# SSDR.net
KiCad netlist of a schematic drawn in Altium Designer
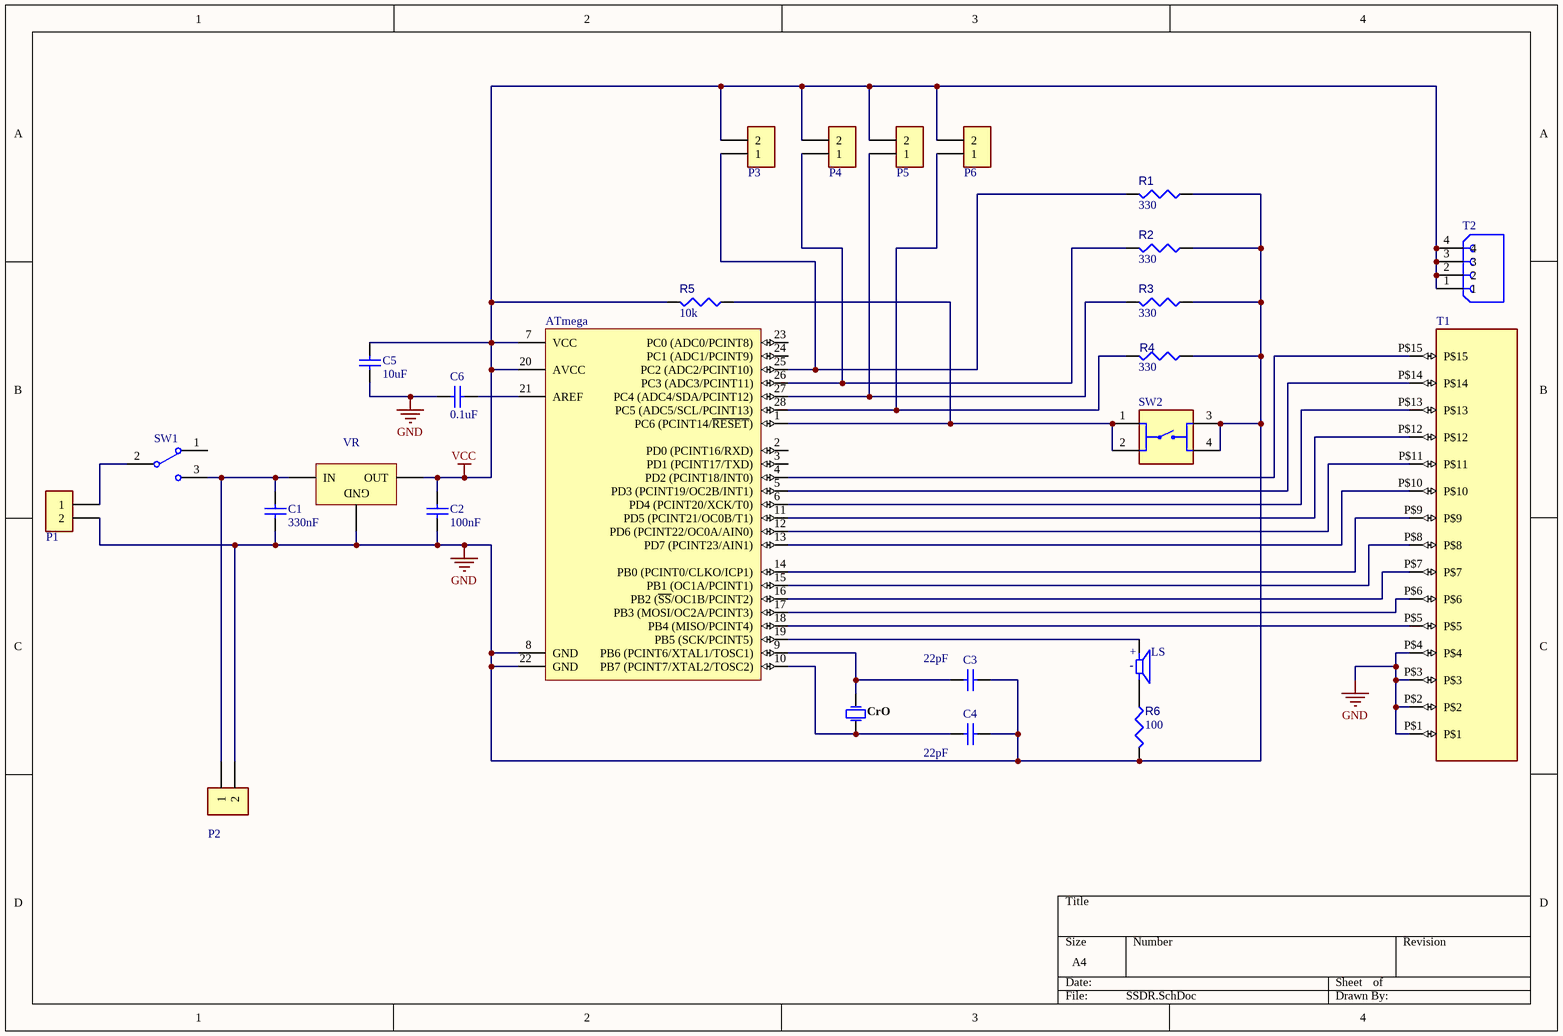
[diagram p0: SSDR.SchDoc]

(export (version "E")
  (design (tool "Eeschema 10.0.6"))
  (components
    (comp (ref "ATmega")
      (value "ATMEGA328P-PU")
      (footprint "ATML-28P3")
      (fields (field (name "MANUFACTURER") "Atmel"))
      (libsource (lib "University of Moratuwa") (part "MC-8B-ATM48-IL28"))
    )
    (comp (ref "C1")
      (value "330nF")
      (footprint "KEMT-C315-THT-2")
      (description "Capacitor, Ceramic, 22 pF, +/-10 %, 100 V, -55 to 125 degC, 2-Pin THD, RoHS, Bulk")
      (libsource (lib "Altium Content Vault") (part "CAP-NP-2"))
    )
    (comp (ref "C2")
      (value "100nF")
      (footprint "KEMT-C315-THT-2")
      (description "Capacitor, Ceramic, 22 pF, +/-10 %, 100 V, -55 to 125 degC, 2-Pin THD, RoHS, Bulk")
      (libsource (lib "Altium Content Vault") (part "CAP-NP-2"))
    )
    (comp (ref "C3")
      (value "22pF")
      (footprint "KEMT-C315-THT-2")
      (description "Capacitor, Ceramic, 22 pF, +/-10 %, 100 V, -55 to 125 degC, 2-Pin THD, RoHS, Bulk")
      (libsource (lib "Altium Content Vault") (part "CAP-NP-2"))
    )
    (comp (ref "C4")
      (value "22pF")
      (footprint "KEMT-C315-THT-2")
      (description "Capacitor, Ceramic, 22 pF, +/-10 %, 100 V, -55 to 125 degC, 2-Pin THD, RoHS, Bulk")
      (libsource (lib "Altium Content Vault") (part "CAP-NP-2"))
    )
    (comp (ref "C5")
      (value "10uF")
      (footprint "KEMT-C315-THT-2")
      (description "Capacitor, Ceramic, 22 pF, +/-10 %, 100 V, -55 to 125 degC, 2-Pin THD, RoHS, Bulk")
      (libsource (lib "Altium Content Vault") (part "CAP-NP-2"))
    )
    (comp (ref "C6")
      (value "0.1uF")
      (footprint "KEMT-C315-THT-2")
      (description "Capacitor, Ceramic, 22 pF, +/-10 %, 100 V, -55 to 125 degC, 2-Pin THD, RoHS, Bulk")
      (libsource (lib "Altium Content Vault") (part "CAP-NP-2"))
    )
    (comp (ref "CrO")
      (value "FOXSLF/160-20")
      (footprint "FOX-FOXSLF160-20")
      (description "Resistance Weld Thru-Hole Crystal, 16 MHz, -20 to 70 degC, 2-Pin THD, RoHS, Bulk")
      (fields (field (name "TOLERANCE") "1%"))
      (libsource (lib "Altium Content Vault") (part "XTAL-1-2-2"))
    )
    (comp (ref "LS")
      (value "PKM17EPP-2002-B0")
      (footprint "SPKR_PKM17EPP-2002-B0")
      (description "Buzzers Transducer, Externally Driven Piezo 3V 2kHz 70dB @ 3V, 10cm Through Hole PC Pins")
      (libsource (lib "University of Moratuwa") (part "PKM17EPP-2002-B0"))
    )
    (comp (ref "P1")
      (value "282837-2")
      (footprint "TE_282837-2")
      (fields (field (name "MF") "TE Connectivity"))
      (libsource (lib "") (part "282837-2_2"))
    )
    (comp (ref "P2")
      (value "282837-2")
      (footprint "TE_282837-2")
      (fields (field (name "MF") "TE Connectivity"))
      (libsource (lib "") (part "282837-2_1"))
    )
    (comp (ref "P3")
      (value "282837-2")
      (footprint "TE_282837-2")
      (fields (field (name "MF") "TE Connectivity"))
      (libsource (lib "University of Moratuwa") (part "282837-2"))
    )
    (comp (ref "P4")
      (value "282837-2")
      (footprint "TE_282837-2")
      (fields (field (name "MF") "TE Connectivity"))
      (libsource (lib "University of Moratuwa") (part "282837-2"))
    )
    (comp (ref "P5")
      (value "282837-2")
      (footprint "TE_282837-2")
      (fields (field (name "MF") "TE Connectivity"))
      (libsource (lib "University of Moratuwa") (part "282837-2"))
    )
    (comp (ref "P6")
      (value "282837-2")
      (footprint "TE_282837-2")
      (fields (field (name "MF") "TE Connectivity"))
      (libsource (lib "University of Moratuwa") (part "282837-2"))
    )
    (comp (ref "R1")
      (value "330")
      (footprint "RESA60-630X240")
      (description "RES 470K OHM 5% 1/4W AXIAL")
      (fields (field (name "POWER") "250mW") (field (name "TOLERANCE") "1%"))
      (libsource (lib "University of Moratuwa") (part "RES-2"))
    )
    (comp (ref "R2")
      (value "330")
      (footprint "RESA60-630X240")
      (description "RES 470K OHM 5% 1/4W AXIAL")
      (fields (field (name "POWER") "250mW") (field (name "TOLERANCE") "1%"))
      (libsource (lib "University of Moratuwa") (part "RES-2"))
    )
    (comp (ref "R3")
      (value "330")
      (footprint "RESA60-630X240")
      (description "RES 470K OHM 5% 1/4W AXIAL")
      (fields (field (name "POWER") "250mW") (field (name "TOLERANCE") "1%"))
      (libsource (lib "University of Moratuwa") (part "RES-2"))
    )
    (comp (ref "R4")
      (value "330")
      (footprint "RESA60-630X240")
      (description "RES 470K OHM 5% 1/4W AXIAL")
      (fields (field (name "POWER") "250mW") (field (name "TOLERANCE") "1%"))
      (libsource (lib "University of Moratuwa") (part "RES-2"))
    )
    (comp (ref "R5")
      (value "10k")
      (footprint "RESA60-630X240")
      (description "RES 470K OHM 5% 1/4W AXIAL")
      (fields (field (name "POWER") "250mW") (field (name "TOLERANCE") "1%"))
      (libsource (lib "University of Moratuwa") (part "RES-2"))
    )
    (comp (ref "R6")
      (value "100")
      (footprint "RESA60-630X240")
      (description "RES 470K OHM 5% 1/4W AXIAL")
      (fields (field (name "POWER") "250mW") (field (name "TOLERANCE") "1%"))
      (libsource (lib "University of Moratuwa") (part "RES-2"))
    )
    (comp (ref "SW1")
      (value "EG1218")
      (footprint "ESWI-EG1218_V")
      (description "Slide Switch, SPDT, 500 V, -20 to 70 degC, 3-Pin THD, RoHS, Bulk")
      (fields (field (name "MANUFACTURER") "E-Switch"))
      (libsource (lib "University of Moratuwa") (part "SW-SPDT-3_B"))
    )
    (comp (ref "SW2")
      (value "1825910-6")
      (footprint "SW_1825910-6-4")
      (description "Switch Push Button OFF (ON) SPST Round Button 0.05A 24VDC Momentary Contact PC Pins Thru-Hole")
      (fields (field (name "DIGI-KEY_PART_NUMBER") "450-1650-ND") (field (name "MF") "TE Connectivity"))
      (libsource (lib "University of Moratuwa") (part "1825910-6"))
    )
    (comp (ref "T1")
      (value "PPTC151LFBN-RC")
      (footprint "PPTC151LFBN-RC")
      (description "15 Position Header Connector Through Hole")
      (fields (field (name "MF") "Sullins Connector"))
      (libsource (lib "University of Moratuwa") (part "PPTC151LFBN-RC"))
    )
    (comp (ref "T2")
      (value "PPTC041LFBN-RC")
      (footprint "SULLINS_PPTC041LFBN-RC")
      (description "4 Position Header Connector 0.100 (2.54mm) Through Hole Tin")
      (fields (field (name "MF") "Sullins Connector") (field (name "DIGI-KEY_PART_NUMBER") "S7002-ND"))
      (libsource (lib "University of Moratuwa") (part "PPTC041LFBN-RC"))
    )
    (comp (ref "VR")
      (value "L7805CV")
      (footprint "TO220")
      (fields (field (name "MANUFACTURER") "STMicroelectronics"))
      (libsource (lib "University of Moratuwa") (part "PM-REG-L4940-SIL3"))
    )
  )
  (nets
    (net (code "1") (name "GND") (class "Default")
      (node (ref "ATmega") (pin "22") (pinfunction "GND_22") (pintype "power_in"))
      (node (ref "ATmega") (pin "8") (pinfunction "GND_8") (pintype "power_in"))
      (node (ref "C1") (pin "1") (pinfunction "1_1") (pintype "passive"))
      (node (ref "C2") (pin "1") (pinfunction "1_1") (pintype "passive"))
      (node (ref "C3") (pin "2") (pinfunction "2_2") (pintype "passive"))
      (node (ref "C4") (pin "2") (pinfunction "2_2") (pintype "passive"))
      (node (ref "C5") (pin "1") (pinfunction "1_1") (pintype "passive"))
      (node (ref "C6") (pin "2") (pinfunction "2_2") (pintype "passive"))
      (node (ref "P1") (pin "2") (pinfunction "2_2") (pintype "passive"))
      (node (ref "P2") (pin "2") (pinfunction "2_2") (pintype "passive"))
      (node (ref "R1") (pin "1") (pinfunction "1_1") (pintype "passive"))
      (node (ref "R2") (pin "1") (pinfunction "1_1") (pintype "passive"))
      (node (ref "R3") (pin "1") (pinfunction "1_1") (pintype "passive"))
      (node (ref "R4") (pin "1") (pinfunction "1_1") (pintype "passive"))
      (node (ref "R6") (pin "2") (pinfunction "2_2") (pintype "passive"))
      (node (ref "SW2") (pin "3") (pinfunction "3_3") (pintype "passive"))
      (node (ref "SW2") (pin "4") (pinfunction "4_4") (pintype "passive"))
      (node (ref "T1") (pin "P$1") (pinfunction "P$1_P$1") (pintype "bidirectional"))
      (node (ref "T1") (pin "P$2") (pinfunction "P$2_P$2") (pintype "bidirectional"))
      (node (ref "T1") (pin "P$3") (pinfunction "P$3_P$3") (pintype "bidirectional"))
      (node (ref "T1") (pin "P$4") (pinfunction "P$4_P$4") (pintype "bidirectional"))
      (node (ref "VR") (pin "2") (pinfunction "GND_2") (pintype "power_in"))
    )
    (net (code "2") (name "Net-(ATmega-AREF)") (class "Default")
      (node (ref "ATmega") (pin "21") (pinfunction "AREF_21") (pintype "power_in"))
      (node (ref "C6") (pin "1") (pinfunction "1_1") (pintype "passive"))
    )
    (net (code "3") (name "Net-(ATmega-PB0_(PCINT0{slash}CLKO{slash}ICP1))") (class "Default")
      (node (ref "ATmega") (pin "14") (pinfunction "PB0_(PCINT0/CLKO/ICP1)_14") (pintype "bidirectional"))
      (node (ref "T1") (pin "P$9") (pinfunction "P$9_P$9") (pintype "bidirectional"))
    )
    (net (code "4") (name "Net-(ATmega-PB1_(OC1A{slash}PCINT1))") (class "Default")
      (node (ref "ATmega") (pin "15") (pinfunction "PB1_(OC1A/PCINT1)_15") (pintype "bidirectional"))
      (node (ref "T1") (pin "P$8") (pinfunction "P$8_P$8") (pintype "bidirectional"))
    )
    (net (code "5") (name "Net-(ATmega-PB2_(~{SS}{slash}OC1B{slash}PCINT2))") (class "Default")
      (node (ref "ATmega") (pin "16") (pinfunction "PB2_(~{SS}/OC1B/PCINT2)_16") (pintype "bidirectional"))
      (node (ref "T1") (pin "P$7") (pinfunction "P$7_P$7") (pintype "bidirectional"))
    )
    (net (code "6") (name "Net-(ATmega-PB3_(MOSI{slash}OC2A{slash}PCINT3))") (class "Default")
      (node (ref "ATmega") (pin "17") (pinfunction "PB3_(MOSI/OC2A/PCINT3)_17") (pintype "bidirectional"))
      (node (ref "T1") (pin "P$6") (pinfunction "P$6_P$6") (pintype "bidirectional"))
    )
    (net (code "7") (name "Net-(ATmega-PB4_(MISO{slash}PCINT4))") (class "Default")
      (node (ref "ATmega") (pin "18") (pinfunction "PB4_(MISO/PCINT4)_18") (pintype "bidirectional"))
      (node (ref "T1") (pin "P$5") (pinfunction "P$5_P$5") (pintype "bidirectional"))
    )
    (net (code "8") (name "Net-(ATmega-PB5_(SCK{slash}PCINT5))") (class "Default")
      (node (ref "ATmega") (pin "19") (pinfunction "PB5_(SCK/PCINT5)_19") (pintype "bidirectional"))
      (node (ref "LS") (pin "P") (pinfunction "P_P") (pintype "passive"))
    )
    (net (code "9") (name "Net-(ATmega-PB6_(PCINT6{slash}XTAL1{slash}TOSC1))") (class "Default")
      (node (ref "ATmega") (pin "9") (pinfunction "PB6_(PCINT6/XTAL1/TOSC1)_9") (pintype "bidirectional"))
      (node (ref "C3") (pin "1") (pinfunction "1_1") (pintype "passive"))
      (node (ref "CrO") (pin "2") (pinfunction "2_2") (pintype "passive"))
    )
    (net (code "10") (name "Net-(ATmega-PB7_(PCINT7{slash}XTAL2{slash}TOSC2))") (class "Default")
      (node (ref "ATmega") (pin "10") (pinfunction "PB7_(PCINT7/XTAL2/TOSC2)_10") (pintype "bidirectional"))
      (node (ref "C4") (pin "1") (pinfunction "1_1") (pintype "passive"))
      (node (ref "CrO") (pin "1") (pinfunction "1_1") (pintype "passive"))
    )
    (net (code "11") (name "Net-(ATmega-PC2_(ADC2{slash}PCINT10))") (class "Default")
      (node (ref "ATmega") (pin "25") (pinfunction "PC2_(ADC2/PCINT10)_25") (pintype "bidirectional"))
      (node (ref "P3") (pin "1") (pinfunction "1_1") (pintype "passive"))
      (node (ref "R1") (pin "2") (pinfunction "2_2") (pintype "passive"))
    )
    (net (code "12") (name "Net-(ATmega-PC3_(ADC3{slash}PCINT11))") (class "Default")
      (node (ref "ATmega") (pin "26") (pinfunction "PC3_(ADC3/PCINT11)_26") (pintype "bidirectional"))
      (node (ref "P4") (pin "1") (pinfunction "1_1") (pintype "passive"))
      (node (ref "R2") (pin "2") (pinfunction "2_2") (pintype "passive"))
    )
    (net (code "13") (name "Net-(ATmega-PC4_(ADC4{slash}SDA{slash}PCINT12))") (class "Default")
      (node (ref "ATmega") (pin "27") (pinfunction "PC4_(ADC4/SDA/PCINT12)_27") (pintype "bidirectional"))
      (node (ref "P5") (pin "1") (pinfunction "1_1") (pintype "passive"))
      (node (ref "R3") (pin "2") (pinfunction "2_2") (pintype "passive"))
    )
    (net (code "14") (name "Net-(ATmega-PC5_(ADC5{slash}SCL{slash}PCINT13))") (class "Default")
      (node (ref "ATmega") (pin "28") (pinfunction "PC5_(ADC5/SCL/PCINT13)_28") (pintype "bidirectional"))
      (node (ref "P6") (pin "1") (pinfunction "1_1") (pintype "passive"))
      (node (ref "R4") (pin "2") (pinfunction "2_2") (pintype "passive"))
    )
    (net (code "15") (name "Net-(ATmega-PC6_(PCINT14{slash}~{RESET}))") (class "Default")
      (node (ref "ATmega") (pin "1") (pinfunction "PC6_(PCINT14/~{RESET})_1") (pintype "bidirectional"))
      (node (ref "R5") (pin "1") (pinfunction "1_1") (pintype "passive"))
      (node (ref "SW2") (pin "1") (pinfunction "1_1") (pintype "passive"))
      (node (ref "SW2") (pin "2") (pinfunction "2_2") (pintype "passive"))
    )
    (net (code "16") (name "Net-(ATmega-PD2_(PCINT18{slash}INT0))") (class "Default")
      (node (ref "ATmega") (pin "4") (pinfunction "PD2_(PCINT18/INT0)_4") (pintype "bidirectional"))
      (node (ref "T1") (pin "P$15") (pinfunction "P$15_P$15") (pintype "bidirectional"))
    )
    (net (code "17") (name "Net-(ATmega-PD3_(PCINT19{slash}OC2B{slash}INT1))") (class "Default")
      (node (ref "ATmega") (pin "5") (pinfunction "PD3_(PCINT19/OC2B/INT1)_5") (pintype "bidirectional"))
      (node (ref "T1") (pin "P$14") (pinfunction "P$14_P$14") (pintype "bidirectional"))
    )
    (net (code "18") (name "Net-(ATmega-PD4_(PCINT20{slash}XCK{slash}T0))") (class "Default")
      (node (ref "ATmega") (pin "6") (pinfunction "PD4_(PCINT20/XCK/T0)_6") (pintype "bidirectional"))
      (node (ref "T1") (pin "P$13") (pinfunction "P$13_P$13") (pintype "bidirectional"))
    )
    (net (code "19") (name "Net-(ATmega-PD5_(PCINT21{slash}OC0B{slash}T1))") (class "Default")
      (node (ref "ATmega") (pin "11") (pinfunction "PD5_(PCINT21/OC0B/T1)_11") (pintype "bidirectional"))
      (node (ref "T1") (pin "P$12") (pinfunction "P$12_P$12") (pintype "bidirectional"))
    )
    (net (code "20") (name "Net-(ATmega-PD6_(PCINT22{slash}OC0A{slash}AIN0))") (class "Default")
      (node (ref "ATmega") (pin "12") (pinfunction "PD6_(PCINT22/OC0A/AIN0)_12") (pintype "bidirectional"))
      (node (ref "T1") (pin "P$11") (pinfunction "P$11_P$11") (pintype "bidirectional"))
    )
    (net (code "21") (name "Net-(ATmega-PD7_(PCINT23{slash}AIN1))") (class "Default")
      (node (ref "ATmega") (pin "13") (pinfunction "PD7_(PCINT23/AIN1)_13") (pintype "bidirectional"))
      (node (ref "T1") (pin "P$10") (pinfunction "P$10_P$10") (pintype "bidirectional"))
    )
    (net (code "22") (name "Net-(LS-PadN)") (class "Default")
      (node (ref "LS") (pin "N") (pinfunction "N_N") (pintype "passive"))
      (node (ref "R6") (pin "1") (pinfunction "1_1") (pintype "passive"))
    )
    (net (code "23") (name "Net-(SW1-COM)") (class "Default")
      (node (ref "P1") (pin "1") (pinfunction "1_1") (pintype "passive"))
      (node (ref "SW1") (pin "2") (pinfunction "COM_2") (pintype "passive"))
    )
    (net (code "24") (name "Net-(VR-IN)") (class "Default")
      (node (ref "C1") (pin "2") (pinfunction "2_2") (pintype "passive"))
      (node (ref "P2") (pin "1") (pinfunction "1_1") (pintype "passive"))
      (node (ref "SW1") (pin "3") (pinfunction "3_3") (pintype "passive"))
      (node (ref "VR") (pin "1") (pinfunction "IN_1") (pintype "power_in"))
    )
    (net (code "25") (name "VCC") (class "Default")
      (node (ref "ATmega") (pin "20") (pinfunction "AVCC_20") (pintype "power_in"))
      (node (ref "ATmega") (pin "7") (pinfunction "VCC_7") (pintype "power_in"))
      (node (ref "C2") (pin "2") (pinfunction "2_2") (pintype "passive"))
      (node (ref "C5") (pin "2") (pinfunction "2_2") (pintype "passive"))
      (node (ref "P3") (pin "2") (pinfunction "2_2") (pintype "passive"))
      (node (ref "P4") (pin "2") (pinfunction "2_2") (pintype "passive"))
      (node (ref "P5") (pin "2") (pinfunction "2_2") (pintype "passive"))
      (node (ref "P6") (pin "2") (pinfunction "2_2") (pintype "passive"))
      (node (ref "R5") (pin "2") (pinfunction "2_2") (pintype "passive"))
      (node (ref "T2") (pin "1") (pinfunction "1_1") (pintype "passive"))
      (node (ref "T2") (pin "2") (pinfunction "2_2") (pintype "passive"))
      (node (ref "T2") (pin "3") (pinfunction "3_3") (pintype "passive"))
      (node (ref "T2") (pin "4") (pinfunction "4_4") (pintype "passive"))
      (node (ref "VR") (pin "3") (pinfunction "OUT_3") (pintype "power_in"))
    )
    (net (code "26") (name "unconnected-(ATmega-PC0_(ADC0{slash}PCINT8)-Pad23)") (class "Default")
      (node (ref "ATmega") (pin "23") (pinfunction "PC0_(ADC0/PCINT8)_23") (pintype "bidirectional"))
    )
    (net (code "27") (name "unconnected-(ATmega-PC1_(ADC1{slash}PCINT9)-Pad24)") (class "Default")
      (node (ref "ATmega") (pin "24") (pinfunction "PC1_(ADC1/PCINT9)_24") (pintype "bidirectional"))
    )
    (net (code "28") (name "unconnected-(ATmega-PD0_(PCINT16{slash}RXD)-Pad2)") (class "Default")
      (node (ref "ATmega") (pin "2") (pinfunction "PD0_(PCINT16/RXD)_2") (pintype "bidirectional"))
    )
    (net (code "29") (name "unconnected-(ATmega-PD1_(PCINT17{slash}TXD)-Pad3)") (class "Default")
      (node (ref "ATmega") (pin "3") (pinfunction "PD1_(PCINT17/TXD)_3") (pintype "bidirectional"))
    )
    (net (code "30") (name "unconnected-(SW1-Pad1)") (class "Default")
      (node (ref "SW1") (pin "1") (pinfunction "1_1") (pintype "passive"))
    )
  )
)
